# nano.net
KiCad netlist of a schematic drawn in EAGLE
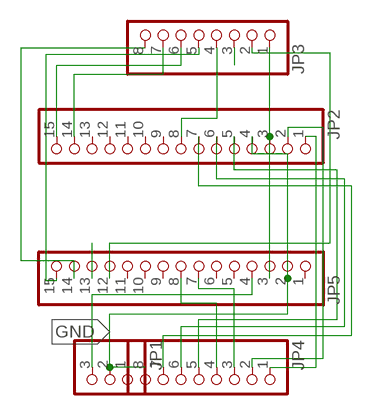
[diagram p0: schematic, sheet 1]

(export (version "E")
  (design (tool "Eeschema 10.0.6"))
  (components
    (comp (ref "JP1")
      (value "PINHD-1X3CB")
      (footprint "eagle-import:1X03-CLEANBIG")
      (libsource (lib "eagle-import") (part "PINHD-1X3CB"))
    )
    (comp (ref "JP2")
      (value "PINHD-1X15")
      (footprint "eagle-import:1X15")
      (libsource (lib "eagle-import") (part "PINHD-1X15"))
    )
    (comp (ref "JP3")
      (value "PINHD-1X8CLEANBIG")
      (footprint "eagle-import:1X08-CLEANBIG")
      (libsource (lib "eagle-import") (part "PINHD-1X8CLEANBIG"))
    )
    (comp (ref "JP4")
      (value "PINHD-1X8CLEANBIG")
      (footprint "eagle-import:1X08-CLEANBIG")
      (libsource (lib "eagle-import") (part "PINHD-1X8CLEANBIG"))
    )
    (comp (ref "JP5")
      (value "PINHD-1X15")
      (footprint "eagle-import:1X15")
      (libsource (lib "eagle-import") (part "PINHD-1X15"))
    )
  )
  (nets
    (net (code "1") (name "GND") (class "Default")
      (node (ref "JP1") (pin "2") (pinfunction "2_2") (pintype "passive"))
      (node (ref "JP2") (pin "4") (pinfunction "4_4") (pintype "passive"))
      (node (ref "JP4") (pin "8") (pinfunction "8_8") (pintype "passive"))
      (node (ref "JP5") (pin "2") (pinfunction "2_2") (pintype "passive"))
    )
    (net (code "2") (name "Net-(JP1-Pad3)") (class "Default")
      (node (ref "JP1") (pin "3") (pinfunction "3_3") (pintype "passive"))
      (node (ref "JP5") (pin "4") (pinfunction "4_4") (pintype "passive"))
    )
    (net (code "3") (name "Net-(JP2-Pad1)") (class "Default")
      (node (ref "JP2") (pin "1") (pinfunction "1_1") (pintype "passive"))
      (node (ref "JP4") (pin "1") (pinfunction "1_1") (pintype "passive"))
    )
    (net (code "4") (name "Net-(JP2-Pad2)") (class "Default")
      (node (ref "JP2") (pin "2") (pinfunction "2_2") (pintype "passive"))
      (node (ref "JP4") (pin "2") (pinfunction "2_2") (pintype "passive"))
    )
    (net (code "5") (name "Net-(JP2-Pad3)") (class "Default")
      (node (ref "JP2") (pin "3") (pinfunction "3_3") (pintype "passive"))
      (node (ref "JP3") (pin "1") (pinfunction "1_1") (pintype "passive"))
      (node (ref "JP5") (pin "3") (pinfunction "3_3") (pintype "passive"))
    )
    (net (code "6") (name "Net-(JP2-Pad5)") (class "Default")
      (node (ref "JP2") (pin "5") (pinfunction "5_5") (pintype "passive"))
      (node (ref "JP4") (pin "5") (pinfunction "5_5") (pintype "passive"))
    )
    (net (code "7") (name "Net-(JP2-Pad6)") (class "Default")
      (node (ref "JP2") (pin "6") (pinfunction "6_6") (pintype "passive"))
      (node (ref "JP4") (pin "6") (pinfunction "6_6") (pintype "passive"))
    )
    (net (code "8") (name "Net-(JP2-Pad7)") (class "Default")
      (node (ref "JP2") (pin "7") (pinfunction "7_7") (pintype "passive"))
      (node (ref "JP4") (pin "7") (pinfunction "7_7") (pintype "passive"))
    )
    (net (code "9") (name "Net-(JP2-Pad8)") (class "Default")
      (node (ref "JP2") (pin "8") (pinfunction "8_8") (pintype "passive"))
      (node (ref "JP3") (pin "4") (pinfunction "4_4") (pintype "passive"))
    )
    (net (code "10") (name "Net-(JP2-Pad14)") (class "Default")
      (node (ref "JP2") (pin "14") (pinfunction "14_14") (pintype "passive"))
      (node (ref "JP3") (pin "7") (pinfunction "7_7") (pintype "passive"))
    )
    (net (code "11") (name "Net-(JP2-Pad15)") (class "Default")
      (node (ref "JP2") (pin "15") (pinfunction "15_15") (pintype "passive"))
      (node (ref "JP3") (pin "6") (pinfunction "6_6") (pintype "passive"))
    )
    (net (code "12") (name "Net-(JP3-Pad2)") (class "Default")
      (node (ref "JP3") (pin "2") (pinfunction "2_2") (pintype "passive"))
      (node (ref "JP5") (pin "12") (pinfunction "12_12") (pintype "passive"))
    )
    (net (code "13") (name "Net-(JP3-Pad5)") (class "Default")
      (node (ref "JP3") (pin "5") (pinfunction "5_5") (pintype "passive"))
      (node (ref "JP5") (pin "15") (pinfunction "15_15") (pintype "passive"))
    )
    (net (code "14") (name "Net-(JP3-Pad8)") (class "Default")
      (node (ref "JP3") (pin "8") (pinfunction "8_8") (pintype "passive"))
      (node (ref "JP5") (pin "14") (pinfunction "14_14") (pintype "passive"))
    )
    (net (code "15") (name "Net-(JP4-Pad3)") (class "Default")
      (node (ref "JP4") (pin "3") (pinfunction "3_3") (pintype "passive"))
      (node (ref "JP5") (pin "7") (pinfunction "7_7") (pintype "passive"))
    )
    (net (code "16") (name "Net-(JP4-Pad4)") (class "Default")
      (node (ref "JP4") (pin "4") (pinfunction "4_4") (pintype "passive"))
      (node (ref "JP5") (pin "8") (pinfunction "8_8") (pintype "passive"))
    )
    (net (code "17") (name "unconnected-(JP1-Pad1)") (class "Default")
      (node (ref "JP1") (pin "1") (pinfunction "1_1") (pintype "passive"))
    )
    (net (code "18") (name "unconnected-(JP2-Pad9)") (class "Default")
      (node (ref "JP2") (pin "9") (pinfunction "9_9") (pintype "passive"))
    )
    (net (code "19") (name "unconnected-(JP2-Pad10)") (class "Default")
      (node (ref "JP2") (pin "10") (pinfunction "10_10") (pintype "passive"))
    )
    (net (code "20") (name "unconnected-(JP2-Pad11)") (class "Default")
      (node (ref "JP2") (pin "11") (pinfunction "11_11") (pintype "passive"))
    )
    (net (code "21") (name "unconnected-(JP2-Pad12)") (class "Default")
      (node (ref "JP2") (pin "12") (pinfunction "12_12") (pintype "passive"))
    )
    (net (code "22") (name "unconnected-(JP2-Pad13)") (class "Default")
      (node (ref "JP2") (pin "13") (pinfunction "13_13") (pintype "passive"))
    )
    (net (code "23") (name "unconnected-(JP3-Pad3)") (class "Default")
      (node (ref "JP3") (pin "3") (pinfunction "3_3") (pintype "passive"))
    )
    (net (code "24") (name "unconnected-(JP5-Pad1)") (class "Default")
      (node (ref "JP5") (pin "1") (pinfunction "1_1") (pintype "passive"))
    )
    (net (code "25") (name "unconnected-(JP5-Pad5)") (class "Default")
      (node (ref "JP5") (pin "5") (pinfunction "5_5") (pintype "passive"))
    )
    (net (code "26") (name "unconnected-(JP5-Pad6)") (class "Default")
      (node (ref "JP5") (pin "6") (pinfunction "6_6") (pintype "passive"))
    )
    (net (code "27") (name "unconnected-(JP5-Pad9)") (class "Default")
      (node (ref "JP5") (pin "9") (pinfunction "9_9") (pintype "passive"))
    )
    (net (code "28") (name "unconnected-(JP5-Pad10)") (class "Default")
      (node (ref "JP5") (pin "10") (pinfunction "10_10") (pintype "passive"))
    )
    (net (code "29") (name "unconnected-(JP5-Pad11)") (class "Default")
      (node (ref "JP5") (pin "11") (pinfunction "11_11") (pintype "passive"))
    )
    (net (code "30") (name "unconnected-(JP5-Pad13)") (class "Default")
      (node (ref "JP5") (pin "13") (pinfunction "13_13") (pintype "passive"))
    )
  )
)
